# Taster.net
KiCad netlist of a schematic drawn in EAGLE
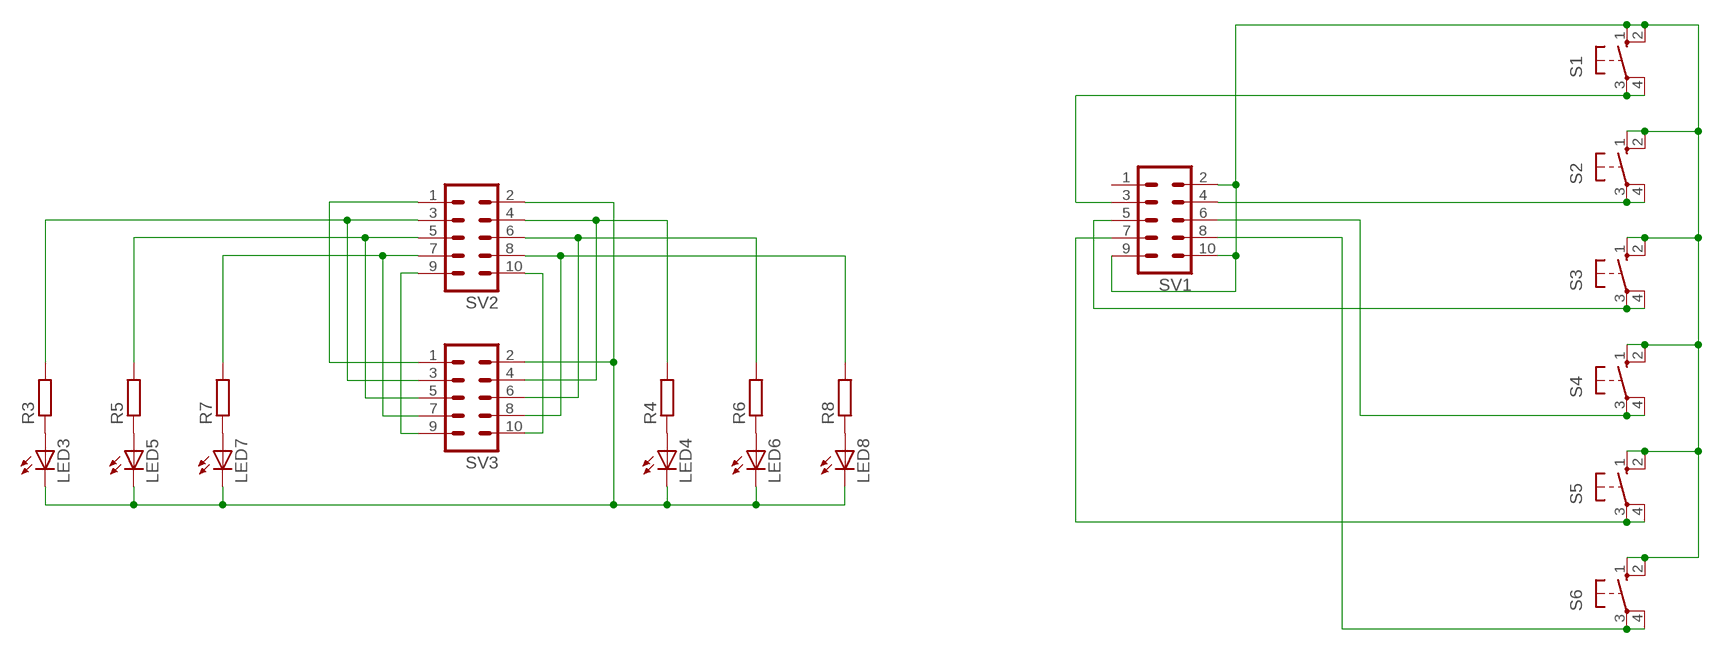
[diagram p0: schematic, sheet 1]

(export (version "E")
  (design (tool "Eeschema 10.0.6"))
  (components
    (comp (ref "LED3")
      (value "LED3MM")
      (footprint "eagle-import:LED3MM")
      (libsource (lib "eagle-import") (part "LED3MM"))
    )
    (comp (ref "LED4")
      (value "LED3MM")
      (footprint "eagle-import:LED3MM")
      (libsource (lib "eagle-import") (part "LED3MM"))
    )
    (comp (ref "LED5")
      (value "LED3MM")
      (footprint "eagle-import:LED3MM")
      (libsource (lib "eagle-import") (part "LED3MM"))
    )
    (comp (ref "LED6")
      (value "LED3MM")
      (footprint "eagle-import:LED3MM")
      (libsource (lib "eagle-import") (part "LED3MM"))
    )
    (comp (ref "LED7")
      (value "LED3MM")
      (footprint "eagle-import:LED3MM")
      (libsource (lib "eagle-import") (part "LED3MM"))
    )
    (comp (ref "LED8")
      (value "LED3MM")
      (footprint "eagle-import:LED3MM")
      (libsource (lib "eagle-import") (part "LED3MM"))
    )
    (comp (ref "R3")
      (value "R-EU_0207/2V")
      (footprint "eagle-import:0207_2V")
      (libsource (lib "eagle-import") (part "R-EU_0207/2V"))
    )
    (comp (ref "R4")
      (value "R-EU_0207/2V")
      (footprint "eagle-import:0207_2V")
      (libsource (lib "eagle-import") (part "R-EU_0207/2V"))
    )
    (comp (ref "R5")
      (value "R-EU_0207/2V")
      (footprint "eagle-import:0207_2V")
      (libsource (lib "eagle-import") (part "R-EU_0207/2V"))
    )
    (comp (ref "R6")
      (value "R-EU_0207/2V")
      (footprint "eagle-import:0207_2V")
      (libsource (lib "eagle-import") (part "R-EU_0207/2V"))
    )
    (comp (ref "R7")
      (value "R-EU_0207/2V")
      (footprint "eagle-import:0207_2V")
      (libsource (lib "eagle-import") (part "R-EU_0207/2V"))
    )
    (comp (ref "R8")
      (value "R-EU_0207/2V")
      (footprint "eagle-import:0207_2V")
      (libsource (lib "eagle-import") (part "R-EU_0207/2V"))
    )
    (comp (ref "S1")
      (value "10-XX")
      (footprint "eagle-import:B3F-10XX")
      (fields (field (name "MPN") "B3F-1000"))
      (libsource (lib "eagle-import") (part "10-XX"))
    )
    (comp (ref "S2")
      (value "10-XX")
      (footprint "eagle-import:B3F-10XX")
      (fields (field (name "MPN") "B3F-1000"))
      (libsource (lib "eagle-import") (part "10-XX"))
    )
    (comp (ref "S3")
      (value "10-XX")
      (footprint "eagle-import:B3F-10XX")
      (fields (field (name "MPN") "B3F-1000"))
      (libsource (lib "eagle-import") (part "10-XX"))
    )
    (comp (ref "S4")
      (value "10-XX")
      (footprint "eagle-import:B3F-10XX")
      (fields (field (name "MPN") "B3F-1000"))
      (libsource (lib "eagle-import") (part "10-XX"))
    )
    (comp (ref "S5")
      (value "10-XX")
      (footprint "eagle-import:B3F-10XX")
      (fields (field (name "MPN") "B3F-1000"))
      (libsource (lib "eagle-import") (part "10-XX"))
    )
    (comp (ref "S6")
      (value "10-XX")
      (footprint "eagle-import:B3F-10XX")
      (fields (field (name "MPN") "B3F-1000"))
      (libsource (lib "eagle-import") (part "10-XX"))
    )
    (comp (ref "SV1")
      (value "ML10")
      (footprint "eagle-import:ML10")
      (libsource (lib "eagle-import") (part "ML10"))
    )
    (comp (ref "SV2")
      (value "ML10")
      (footprint "eagle-import:ML10")
      (libsource (lib "eagle-import") (part "ML10"))
    )
    (comp (ref "SV3")
      (value "ML10")
      (footprint "eagle-import:ML10")
      (libsource (lib "eagle-import") (part "ML10"))
    )
  )
  (nets
    (net (code "1") (name "Net-(LED3-C)") (class "Default")
      (node (ref "LED3") (pin "K") (pinfunction "C_K") (pintype "passive"))
      (node (ref "LED4") (pin "K") (pinfunction "C_K") (pintype "passive"))
      (node (ref "LED5") (pin "K") (pinfunction "C_K") (pintype "passive"))
      (node (ref "LED6") (pin "K") (pinfunction "C_K") (pintype "passive"))
      (node (ref "LED7") (pin "K") (pinfunction "C_K") (pintype "passive"))
      (node (ref "LED8") (pin "K") (pinfunction "C_K") (pintype "passive"))
      (node (ref "SV2") (pin "2") (pinfunction "2_2") (pintype "passive"))
      (node (ref "SV3") (pin "2") (pinfunction "2_2") (pintype "passive"))
    )
    (net (code "2") (name "Net-(LED3-PadA)") (class "Default")
      (node (ref "LED3") (pin "A") (pinfunction "A_A") (pintype "passive"))
      (node (ref "R3") (pin "1") (pinfunction "1_1") (pintype "passive"))
    )
    (net (code "3") (name "Net-(LED4-PadA)") (class "Default")
      (node (ref "LED4") (pin "A") (pinfunction "A_A") (pintype "passive"))
      (node (ref "R4") (pin "1") (pinfunction "1_1") (pintype "passive"))
    )
    (net (code "4") (name "Net-(LED5-PadA)") (class "Default")
      (node (ref "LED5") (pin "A") (pinfunction "A_A") (pintype "passive"))
      (node (ref "R5") (pin "1") (pinfunction "1_1") (pintype "passive"))
    )
    (net (code "5") (name "Net-(LED6-PadA)") (class "Default")
      (node (ref "LED6") (pin "A") (pinfunction "A_A") (pintype "passive"))
      (node (ref "R6") (pin "1") (pinfunction "1_1") (pintype "passive"))
    )
    (net (code "6") (name "Net-(LED7-PadA)") (class "Default")
      (node (ref "LED7") (pin "A") (pinfunction "A_A") (pintype "passive"))
      (node (ref "R7") (pin "1") (pinfunction "1_1") (pintype "passive"))
    )
    (net (code "7") (name "Net-(LED8-PadA)") (class "Default")
      (node (ref "LED8") (pin "A") (pinfunction "A_A") (pintype "passive"))
      (node (ref "R8") (pin "1") (pinfunction "1_1") (pintype "passive"))
    )
    (net (code "8") (name "Net-(R3-Pad2)") (class "Default")
      (node (ref "R3") (pin "2") (pinfunction "2_2") (pintype "passive"))
      (node (ref "SV2") (pin "3") (pinfunction "3_3") (pintype "passive"))
      (node (ref "SV3") (pin "3") (pinfunction "3_3") (pintype "passive"))
    )
    (net (code "9") (name "Net-(R4-Pad2)") (class "Default")
      (node (ref "R4") (pin "2") (pinfunction "2_2") (pintype "passive"))
      (node (ref "SV2") (pin "4") (pinfunction "4_4") (pintype "passive"))
      (node (ref "SV3") (pin "4") (pinfunction "4_4") (pintype "passive"))
    )
    (net (code "10") (name "Net-(R5-Pad2)") (class "Default")
      (node (ref "R5") (pin "2") (pinfunction "2_2") (pintype "passive"))
      (node (ref "SV2") (pin "5") (pinfunction "5_5") (pintype "passive"))
      (node (ref "SV3") (pin "5") (pinfunction "5_5") (pintype "passive"))
    )
    (net (code "11") (name "Net-(R6-Pad2)") (class "Default")
      (node (ref "R6") (pin "2") (pinfunction "2_2") (pintype "passive"))
      (node (ref "SV2") (pin "6") (pinfunction "6_6") (pintype "passive"))
      (node (ref "SV3") (pin "6") (pinfunction "6_6") (pintype "passive"))
    )
    (net (code "12") (name "Net-(R7-Pad2)") (class "Default")
      (node (ref "R7") (pin "2") (pinfunction "2_2") (pintype "passive"))
      (node (ref "SV2") (pin "7") (pinfunction "7_7") (pintype "passive"))
      (node (ref "SV3") (pin "7") (pinfunction "7_7") (pintype "passive"))
    )
    (net (code "13") (name "Net-(R8-Pad2)") (class "Default")
      (node (ref "R8") (pin "2") (pinfunction "2_2") (pintype "passive"))
      (node (ref "SV2") (pin "8") (pinfunction "8_8") (pintype "passive"))
      (node (ref "SV3") (pin "8") (pinfunction "8_8") (pintype "passive"))
    )
    (net (code "14") (name "Net-(S1-P)") (class "Default")
      (node (ref "S1") (pin "3") (pinfunction "P_3") (pintype "passive"))
      (node (ref "S1") (pin "4") (pinfunction "P1_4") (pintype "passive"))
      (node (ref "SV1") (pin "3") (pinfunction "3_3") (pintype "passive"))
    )
    (net (code "15") (name "Net-(S1-S)") (class "Default")
      (node (ref "S1") (pin "1") (pinfunction "S_1") (pintype "passive"))
      (node (ref "S1") (pin "2") (pinfunction "S1_2") (pintype "passive"))
      (node (ref "S2") (pin "1") (pinfunction "S_1") (pintype "passive"))
      (node (ref "S2") (pin "2") (pinfunction "S1_2") (pintype "passive"))
      (node (ref "S3") (pin "1") (pinfunction "S_1") (pintype "passive"))
      (node (ref "S3") (pin "2") (pinfunction "S1_2") (pintype "passive"))
      (node (ref "S4") (pin "1") (pinfunction "S_1") (pintype "passive"))
      (node (ref "S4") (pin "2") (pinfunction "S1_2") (pintype "passive"))
      (node (ref "S5") (pin "1") (pinfunction "S_1") (pintype "passive"))
      (node (ref "S5") (pin "2") (pinfunction "S1_2") (pintype "passive"))
      (node (ref "S6") (pin "1") (pinfunction "S_1") (pintype "passive"))
      (node (ref "S6") (pin "2") (pinfunction "S1_2") (pintype "passive"))
      (node (ref "SV1") (pin "10") (pinfunction "10_10") (pintype "passive"))
      (node (ref "SV1") (pin "2") (pinfunction "2_2") (pintype "passive"))
      (node (ref "SV1") (pin "9") (pinfunction "9_9") (pintype "passive"))
    )
    (net (code "16") (name "Net-(S2-P)") (class "Default")
      (node (ref "S2") (pin "3") (pinfunction "P_3") (pintype "passive"))
      (node (ref "S2") (pin "4") (pinfunction "P1_4") (pintype "passive"))
      (node (ref "SV1") (pin "4") (pinfunction "4_4") (pintype "passive"))
    )
    (net (code "17") (name "Net-(S3-P)") (class "Default")
      (node (ref "S3") (pin "3") (pinfunction "P_3") (pintype "passive"))
      (node (ref "S3") (pin "4") (pinfunction "P1_4") (pintype "passive"))
      (node (ref "SV1") (pin "5") (pinfunction "5_5") (pintype "passive"))
    )
    (net (code "18") (name "Net-(S4-P)") (class "Default")
      (node (ref "S4") (pin "3") (pinfunction "P_3") (pintype "passive"))
      (node (ref "S4") (pin "4") (pinfunction "P1_4") (pintype "passive"))
      (node (ref "SV1") (pin "6") (pinfunction "6_6") (pintype "passive"))
    )
    (net (code "19") (name "Net-(S5-P)") (class "Default")
      (node (ref "S5") (pin "3") (pinfunction "P_3") (pintype "passive"))
      (node (ref "S5") (pin "4") (pinfunction "P1_4") (pintype "passive"))
      (node (ref "SV1") (pin "7") (pinfunction "7_7") (pintype "passive"))
    )
    (net (code "20") (name "Net-(S6-P)") (class "Default")
      (node (ref "S6") (pin "3") (pinfunction "P_3") (pintype "passive"))
      (node (ref "S6") (pin "4") (pinfunction "P1_4") (pintype "passive"))
      (node (ref "SV1") (pin "8") (pinfunction "8_8") (pintype "passive"))
    )
    (net (code "21") (name "Net-(SV2-Pad1)") (class "Default")
      (node (ref "SV2") (pin "1") (pinfunction "1_1") (pintype "passive"))
      (node (ref "SV3") (pin "1") (pinfunction "1_1") (pintype "passive"))
    )
    (net (code "22") (name "Net-(SV2-Pad9)") (class "Default")
      (node (ref "SV2") (pin "9") (pinfunction "9_9") (pintype "passive"))
      (node (ref "SV3") (pin "9") (pinfunction "9_9") (pintype "passive"))
    )
    (net (code "23") (name "Net-(SV2-Pad10)") (class "Default")
      (node (ref "SV2") (pin "10") (pinfunction "10_10") (pintype "passive"))
      (node (ref "SV3") (pin "10") (pinfunction "10_10") (pintype "passive"))
    )
    (net (code "24") (name "unconnected-(SV1-Pad1)") (class "Default")
      (node (ref "SV1") (pin "1") (pinfunction "1_1") (pintype "passive"))
    )
  )
)
